# Altium_radio.net
KiCad netlist of a schematic drawn in Altium Designer
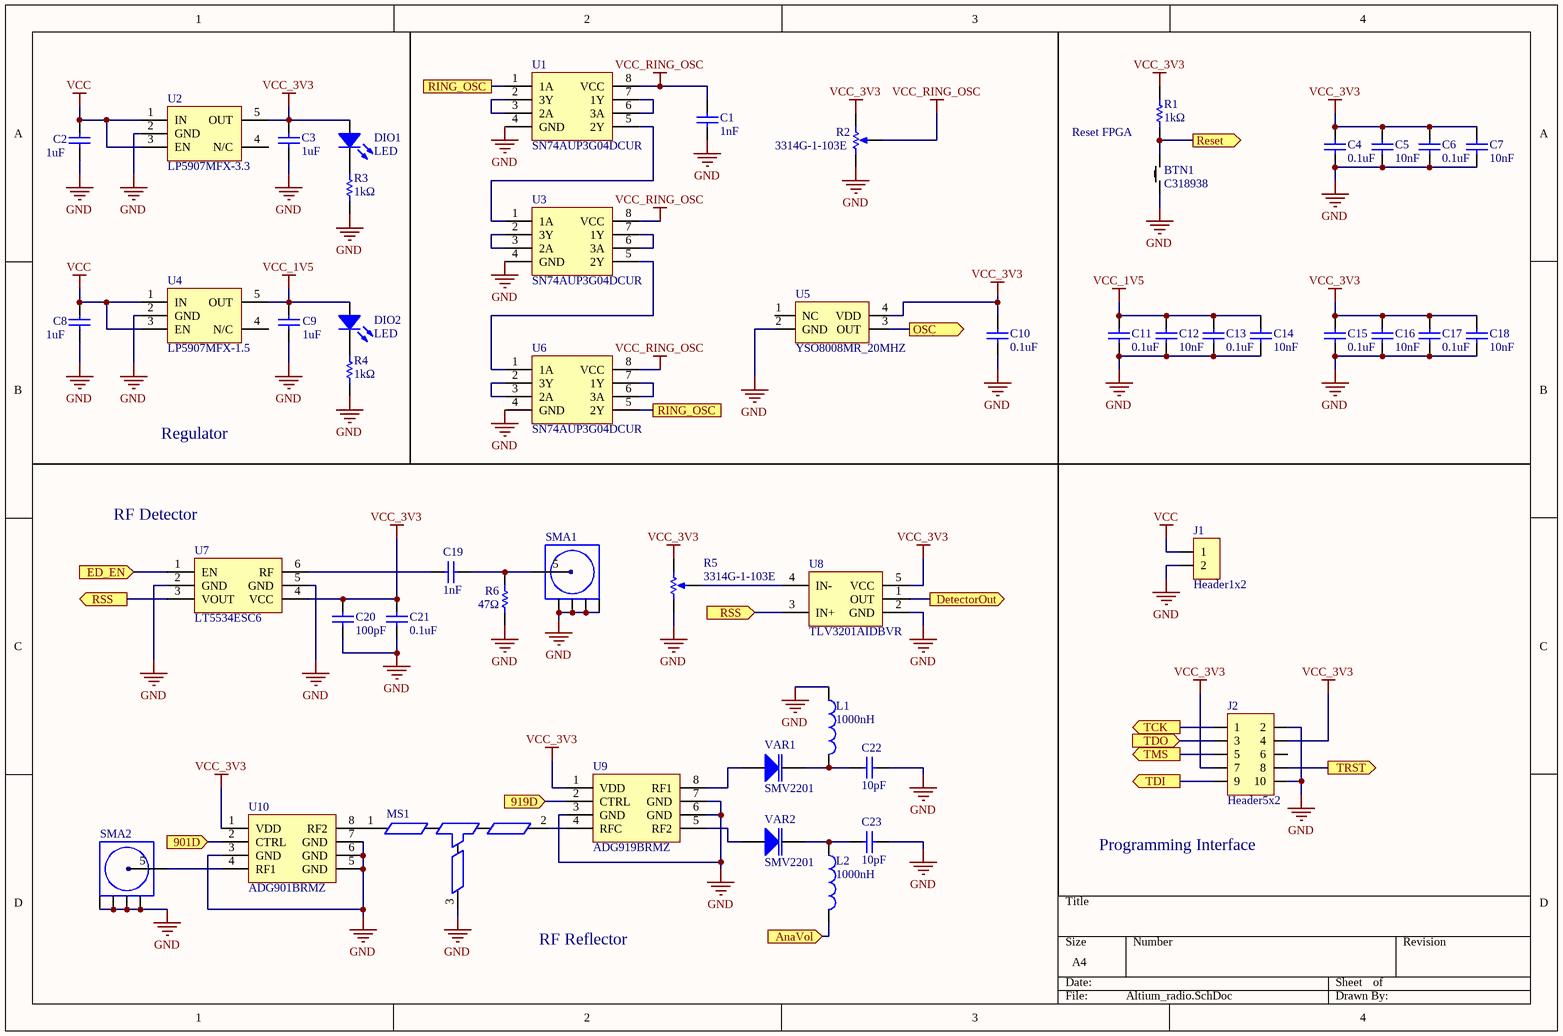
[diagram p0: Altium_radio.SchDoc]

(export (version "E")
  (design (tool "Eeschema 10.0.6"))
  (components
    (comp (ref "BTN1")
      (value "C318938")
      (footprint "C318938")
      (libsource (lib "backscatter") (part "C318938"))
    )
    (comp (ref "C1") (value "1nF") (footprint "C0603") (libsource (lib "backscatter") (part "Cap")))
    (comp (ref "C2") (value "1uF") (footprint "C0603") (libsource (lib "backscatter") (part "Cap")))
    (comp (ref "C3") (value "1uF") (footprint "C0603") (libsource (lib "backscatter") (part "Cap")))
    (comp (ref "C4") (value "0.1uF") (footprint "C0603") (libsource (lib "backscatter") (part "Cap")))
    (comp (ref "C5") (value "10nF") (footprint "C0603") (libsource (lib "backscatter") (part "Cap")))
    (comp (ref "C6") (value "0.1uF") (footprint "C0603") (libsource (lib "backscatter") (part "Cap")))
    (comp (ref "C7") (value "10nF") (footprint "C0603") (libsource (lib "backscatter") (part "Cap")))
    (comp (ref "C8") (value "1uF") (footprint "C0603") (libsource (lib "backscatter") (part "Cap")))
    (comp (ref "C9") (value "1uF") (footprint "C0603") (libsource (lib "backscatter") (part "Cap")))
    (comp (ref "C10") (value "0.1uF") (footprint "C0603") (libsource (lib "backscatter") (part "Cap")))
    (comp (ref "C11") (value "0.1uF") (footprint "C0603") (libsource (lib "backscatter") (part "Cap")))
    (comp (ref "C12") (value "10nF") (footprint "C0603") (libsource (lib "backscatter") (part "Cap")))
    (comp (ref "C13") (value "0.1uF") (footprint "C0603") (libsource (lib "backscatter") (part "Cap")))
    (comp (ref "C14") (value "10nF") (footprint "C0603") (libsource (lib "backscatter") (part "Cap")))
    (comp (ref "C15") (value "0.1uF") (footprint "C0603") (libsource (lib "backscatter") (part "Cap")))
    (comp (ref "C16") (value "10nF") (footprint "C0603") (libsource (lib "backscatter") (part "Cap")))
    (comp (ref "C17") (value "0.1uF") (footprint "C0603") (libsource (lib "backscatter") (part "Cap")))
    (comp (ref "C18") (value "10nF") (footprint "C0603") (libsource (lib "backscatter") (part "Cap")))
    (comp (ref "C19") (value "1nF") (footprint "C0603") (libsource (lib "backscatter") (part "Cap")))
    (comp (ref "C20") (value "100pF") (footprint "C0402") (libsource (lib "backscatter") (part "Cap")))
    (comp (ref "C21") (value "0.1uF") (footprint "C0603") (libsource (lib "backscatter") (part "Cap")))
    (comp (ref "C22") (value "10pF") (footprint "C0402") (libsource (lib "backscatter") (part "Cap")))
    (comp (ref "C23") (value "10pF") (footprint "C0402") (libsource (lib "backscatter") (part "Cap")))
    (comp (ref "DIO1") (value "LED") (footprint "LED0603") (libsource (lib "backscatter") (part "LED")))
    (comp (ref "DIO2") (value "LED") (footprint "LED0603") (libsource (lib "backscatter") (part "LED")))
    (comp (ref "J1")
      (value "Header1x2")
      (footprint "Header1x2")
      (libsource (lib "backscatter") (part "Header1x2"))
    )
    (comp (ref "J2")
      (value "Header5x2")
      (footprint "Header2x5")
      (libsource (lib "backscatter") (part "Header5x2"))
    )
    (comp (ref "L1") (value "1000nH") (footprint "L0805") (libsource (lib "backscatter") (part "Inductor")))
    (comp (ref "L2") (value "1000nH") (footprint "L0805") (libsource (lib "backscatter") (part "Inductor")))
    (comp (ref "MS1") (value "MSTEE") (footprint "MTEE_SMA") (libsource (lib "backscatter") (part "MSTEE")))
    (comp (ref "R1") (value "1kΩ") (footprint "R0603") (libsource (lib "backscatter") (part "Res")))
    (comp (ref "R2")
      (value "3314G-1-103E")
      (footprint "3314G-1-103E")
      (libsource (lib "backscatter") (part "3314G-1-103E"))
    )
    (comp (ref "R3") (value "1kΩ") (footprint "R0603") (libsource (lib "backscatter") (part "Res")))
    (comp (ref "R4") (value "1kΩ") (footprint "R0603") (libsource (lib "backscatter") (part "Res")))
    (comp (ref "R5")
      (value "3314G-1-103E")
      (footprint "3314G-1-103E")
      (libsource (lib "backscatter") (part "3314G-1-103E"))
    )
    (comp (ref "R6") (value "47Ω") (footprint "R0603") (libsource (lib "backscatter") (part "Res")))
    (comp (ref "SMA1") (value "SMA") (footprint "HJ-SMA305") (libsource (lib "") (part "SMA_1")))
    (comp (ref "SMA2") (value "SMA") (footprint "HJ-SMA305") (libsource (lib "backscatter") (part "SMA")))
    (comp (ref "U1")
      (value "SN74AUP3G04DCUR")
      (footprint "SN74AUP3G04DCUR")
      (libsource (lib "backscatter") (part "SN74AUP3G04DCUR"))
    )
    (comp (ref "U2")
      (value "LP5907MFX-3.3")
      (footprint "LP5907MFX-3.3")
      (libsource (lib "backscatter") (part "LP5907MFX-3.3"))
    )
    (comp (ref "U3")
      (value "SN74AUP3G04DCUR")
      (footprint "SN74AUP3G04DCUR")
      (libsource (lib "backscatter") (part "SN74AUP3G04DCUR"))
    )
    (comp (ref "U4")
      (value "LP5907MFX-1.5")
      (footprint "LP5907MFX-1.5")
      (libsource (lib "backscatter") (part "LP5907MFX-1.5"))
    )
    (comp (ref "U5")
      (value "YSO8008MR_20MHZ")
      (footprint "YSO8008MR_20MHz")
      (libsource (lib "backscatter") (part "YSO8008MR_20MHZ"))
    )
    (comp (ref "U6")
      (value "SN74AUP3G04DCUR")
      (footprint "SN74AUP3G04DCUR")
      (libsource (lib "backscatter") (part "SN74AUP3G04DCUR"))
    )
    (comp (ref "U7")
      (value "LT5534ESC6")
      (footprint "LT5534ESC6#TRPBF")
      (libsource (lib "backscatter") (part "LT5534ESC6"))
    )
    (comp (ref "U8")
      (value "TLV3201AIDBVR")
      (footprint "TLV3201AIDBVR")
      (libsource (lib "backscatter") (part "TLV3201AIDBVR"))
    )
    (comp (ref "U9")
      (value "ADG919BRMZ")
      (footprint "ADG919BRMZ")
      (libsource (lib "backscatter") (part "ADG919BRMZ"))
    )
    (comp (ref "U10")
      (value "ADG901BRMZ")
      (footprint "ADG901BRMZ-REEL7")
      (libsource (lib "backscatter") (part "ADG901BRMZ"))
    )
    (comp (ref "VAR1") (value "SMV2201") (footprint "D0402") (libsource (lib "backscatter") (part "VAR")))
    (comp (ref "VAR2") (value "SMV2201") (footprint "D0402") (libsource (lib "backscatter") (part "VAR")))
  )
  (nets
    (net (code "1") (name "/901D") (class "Default")
      (node (ref "U10") (pin "2") (pinfunction "CTRL_2") (pintype "passive"))
    )
    (net (code "2") (name "/919D") (class "Default")
      (node (ref "U9") (pin "2") (pinfunction "CTRL_2") (pintype "passive"))
    )
    (net (code "3") (name "/AnaVol") (class "Default")
      (node (ref "L2") (pin "2") (pinfunction "2_2") (pintype "passive"))
    )
    (net (code "4") (name "/DetectorOut") (class "Default")
      (node (ref "U8") (pin "1") (pinfunction "OUT_1") (pintype "passive"))
    )
    (net (code "5") (name "/ED_EN") (class "Default")
      (node (ref "U7") (pin "1") (pinfunction "EN_1") (pintype "passive"))
    )
    (net (code "6") (name "/OSC") (class "Default")
      (node (ref "U5") (pin "3") (pinfunction "OUT_3") (pintype "passive"))
    )
    (net (code "7") (name "/RING_OSC") (class "Default")
      (node (ref "U1") (pin "1") (pinfunction "1A_1") (pintype "passive"))
      (node (ref "U6") (pin "5") (pinfunction "2Y_5") (pintype "passive"))
    )
    (net (code "8") (name "/RSS") (class "Default")
      (node (ref "U7") (pin "3") (pinfunction "VOUT_3") (pintype "passive"))
      (node (ref "U8") (pin "3") (pinfunction "IN+_3") (pintype "passive"))
    )
    (net (code "9") (name "/Reset") (class "Default")
      (node (ref "BTN1") (pin "2") (pinfunction "2_2") (pintype "passive"))
      (node (ref "R1") (pin "1") (pinfunction "1_1") (pintype "passive"))
    )
    (net (code "10") (name "/TCK") (class "Default")
      (node (ref "J2") (pin "1") (pinfunction "1_1") (pintype "passive"))
    )
    (net (code "11") (name "/TDI") (class "Default")
      (node (ref "J2") (pin "9") (pinfunction "9_9") (pintype "passive"))
    )
    (net (code "12") (name "/TDO") (class "Default")
      (node (ref "J2") (pin "3") (pinfunction "3_3") (pintype "passive"))
    )
    (net (code "13") (name "/TMS") (class "Default")
      (node (ref "J2") (pin "5") (pinfunction "5_5") (pintype "passive"))
    )
    (net (code "14") (name "/TRST") (class "Default")
      (node (ref "J2") (pin "8") (pinfunction "8_8") (pintype "passive"))
    )
    (net (code "15") (name "GND") (class "Default")
      (node (ref "BTN1") (pin "1") (pinfunction "1_1") (pintype "passive"))
      (node (ref "C1") (pin "1") (pinfunction "1_1") (pintype "passive"))
      (node (ref "C10") (pin "2") (pinfunction "2_2") (pintype "passive"))
      (node (ref "C11") (pin "2") (pinfunction "2_2") (pintype "passive"))
      (node (ref "C12") (pin "2") (pinfunction "2_2") (pintype "passive"))
      (node (ref "C13") (pin "2") (pinfunction "2_2") (pintype "passive"))
      (node (ref "C14") (pin "2") (pinfunction "2_2") (pintype "passive"))
      (node (ref "C15") (pin "2") (pinfunction "2_2") (pintype "passive"))
      (node (ref "C16") (pin "2") (pinfunction "2_2") (pintype "passive"))
      (node (ref "C17") (pin "2") (pinfunction "2_2") (pintype "passive"))
      (node (ref "C18") (pin "2") (pinfunction "2_2") (pintype "passive"))
      (node (ref "C2") (pin "1") (pinfunction "1_1") (pintype "passive"))
      (node (ref "C20") (pin "1") (pinfunction "1_1") (pintype "passive"))
      (node (ref "C21") (pin "1") (pinfunction "1_1") (pintype "passive"))
      (node (ref "C22") (pin "2") (pinfunction "2_2") (pintype "passive"))
      (node (ref "C23") (pin "2") (pinfunction "2_2") (pintype "passive"))
      (node (ref "C3") (pin "1") (pinfunction "1_1") (pintype "passive"))
      (node (ref "C4") (pin "2") (pinfunction "2_2") (pintype "passive"))
      (node (ref "C5") (pin "2") (pinfunction "2_2") (pintype "passive"))
      (node (ref "C6") (pin "2") (pinfunction "2_2") (pintype "passive"))
      (node (ref "C7") (pin "2") (pinfunction "2_2") (pintype "passive"))
      (node (ref "C8") (pin "1") (pinfunction "1_1") (pintype "passive"))
      (node (ref "C9") (pin "1") (pinfunction "1_1") (pintype "passive"))
      (node (ref "J1") (pin "2") (pinfunction "2_2") (pintype "passive"))
      (node (ref "J2") (pin "10") (pinfunction "10_10") (pintype "passive"))
      (node (ref "J2") (pin "2") (pinfunction "2_2") (pintype "passive"))
      (node (ref "L1") (pin "1") (pinfunction "1_1") (pintype "passive"))
      (node (ref "MS1") (pin "3") (pinfunction "3_3") (pintype "passive"))
      (node (ref "R2") (pin "3") (pinfunction "CW_3") (pintype "passive"))
      (node (ref "R3") (pin "1") (pinfunction "1_1") (pintype "passive"))
      (node (ref "R4") (pin "1") (pinfunction "1_1") (pintype "passive"))
      (node (ref "R5") (pin "3") (pinfunction "CW_3") (pintype "passive"))
      (node (ref "R6") (pin "1") (pinfunction "1_1") (pintype "passive"))
      (node (ref "SMA1") (pin "1") (pinfunction "GND_1") (pintype "power_in"))
      (node (ref "SMA1") (pin "2") (pinfunction "GND_2") (pintype "power_in"))
      (node (ref "SMA1") (pin "3") (pinfunction "GND_3") (pintype "power_in"))
      (node (ref "SMA1") (pin "4") (pinfunction "GND_4") (pintype "power_in"))
      (node (ref "SMA2") (pin "1") (pinfunction "GND_1") (pintype "power_in"))
      (node (ref "SMA2") (pin "2") (pinfunction "GND_2") (pintype "power_in"))
      (node (ref "SMA2") (pin "3") (pinfunction "GND_3") (pintype "power_in"))
      (node (ref "SMA2") (pin "4") (pinfunction "GND_4") (pintype "power_in"))
      (node (ref "U1") (pin "4") (pinfunction "GND_4") (pintype "power_in"))
      (node (ref "U10") (pin "3") (pinfunction "GND_3") (pintype "power_in"))
      (node (ref "U10") (pin "5") (pinfunction "GND_5") (pintype "power_in"))
      (node (ref "U10") (pin "6") (pinfunction "GND_6") (pintype "power_in"))
      (node (ref "U10") (pin "7") (pinfunction "GND_7") (pintype "power_in"))
      (node (ref "U2") (pin "2") (pinfunction "GND_2") (pintype "power_in"))
      (node (ref "U3") (pin "4") (pinfunction "GND_4") (pintype "power_in"))
      (node (ref "U4") (pin "2") (pinfunction "GND_2") (pintype "power_in"))
      (node (ref "U5") (pin "2") (pinfunction "GND_2") (pintype "passive"))
      (node (ref "U6") (pin "4") (pinfunction "GND_4") (pintype "power_in"))
      (node (ref "U7") (pin "2") (pinfunction "GND_2") (pintype "power_in"))
      (node (ref "U7") (pin "5") (pinfunction "GND_5") (pintype "power_in"))
      (node (ref "U8") (pin "2") (pinfunction "GND_2") (pintype "power_in"))
      (node (ref "U9") (pin "3") (pinfunction "GND_3") (pintype "power_in"))
      (node (ref "U9") (pin "6") (pinfunction "GND_6") (pintype "power_in"))
      (node (ref "U9") (pin "7") (pinfunction "GND_7") (pintype "power_in"))
    )
    (net (code "16") (name "Net-(DIO1-*-Pad2)") (class "Default")
      (node (ref "DIO1") (pin "2") (pinfunction "*_2") (pintype "passive"))
      (node (ref "R3") (pin "2") (pinfunction "2_2") (pintype "passive"))
    )
    (net (code "17") (name "Net-(DIO2-*-Pad2)") (class "Default")
      (node (ref "DIO2") (pin "2") (pinfunction "*_2") (pintype "passive"))
      (node (ref "R4") (pin "2") (pinfunction "2_2") (pintype "passive"))
    )
    (net (code "18") (name "Net-(R5-WIPER)") (class "Default")
      (node (ref "R5") (pin "2") (pinfunction "WIPER_2") (pintype "passive"))
      (node (ref "U8") (pin "4") (pinfunction "IN-_4") (pintype "passive"))
    )
    (net (code "19") (name "Net-(SMA1-SMA_CON)") (class "Default")
      (node (ref "C19") (pin "2") (pinfunction "2_2") (pintype "passive"))
      (node (ref "R6") (pin "2") (pinfunction "2_2") (pintype "passive"))
      (node (ref "SMA1") (pin "5") (pinfunction "SMA_CON_5") (pintype "passive"))
    )
    (net (code "20") (name "Net-(SMA2-SMA_CON)") (class "Default")
      (node (ref "SMA2") (pin "5") (pinfunction "SMA_CON_5") (pintype "passive"))
      (node (ref "U10") (pin "4") (pinfunction "RF1_4") (pintype "passive"))
    )
    (net (code "21") (name "Net-(U1-1Y)") (class "Default")
      (node (ref "U1") (pin "6") (pinfunction "3A_6") (pintype "passive"))
      (node (ref "U1") (pin "7") (pinfunction "1Y_7") (pintype "passive"))
    )
    (net (code "22") (name "Net-(U1-2A)") (class "Default")
      (node (ref "U1") (pin "2") (pinfunction "3Y_2") (pintype "passive"))
      (node (ref "U1") (pin "3") (pinfunction "2A_3") (pintype "passive"))
    )
    (net (code "23") (name "Net-(U1-2Y)") (class "Default")
      (node (ref "U1") (pin "5") (pinfunction "2Y_5") (pintype "passive"))
      (node (ref "U3") (pin "1") (pinfunction "1A_1") (pintype "passive"))
    )
    (net (code "24") (name "Net-(U3-1Y)") (class "Default")
      (node (ref "U3") (pin "6") (pinfunction "3A_6") (pintype "passive"))
      (node (ref "U3") (pin "7") (pinfunction "1Y_7") (pintype "passive"))
    )
    (net (code "25") (name "Net-(U3-2A)") (class "Default")
      (node (ref "U3") (pin "2") (pinfunction "3Y_2") (pintype "passive"))
      (node (ref "U3") (pin "3") (pinfunction "2A_3") (pintype "passive"))
    )
    (net (code "26") (name "Net-(U3-2Y)") (class "Default")
      (node (ref "U3") (pin "5") (pinfunction "2Y_5") (pintype "passive"))
      (node (ref "U6") (pin "1") (pinfunction "1A_1") (pintype "passive"))
    )
    (net (code "27") (name "Net-(U6-1Y)") (class "Default")
      (node (ref "U6") (pin "6") (pinfunction "3A_6") (pintype "passive"))
      (node (ref "U6") (pin "7") (pinfunction "1Y_7") (pintype "passive"))
    )
    (net (code "28") (name "Net-(U6-2A)") (class "Default")
      (node (ref "U6") (pin "2") (pinfunction "3Y_2") (pintype "passive"))
      (node (ref "U6") (pin "3") (pinfunction "2A_3") (pintype "passive"))
    )
    (net (code "29") (name "Net-(U7-RF)") (class "Default")
      (node (ref "C19") (pin "1") (pinfunction "1_1") (pintype "passive"))
      (node (ref "U7") (pin "6") (pinfunction "RF_6") (pintype "passive"))
    )
    (net (code "30") (name "Net-(U9-RF1)") (class "Default")
      (node (ref "U9") (pin "8") (pinfunction "RF1_8") (pintype "passive"))
      (node (ref "VAR1") (pin "2") (pinfunction "A_2") (pintype "passive"))
    )
    (net (code "31") (name "Net-(U9-RF2)") (class "Default")
      (node (ref "U9") (pin "5") (pinfunction "RF2_5") (pintype "passive"))
      (node (ref "VAR2") (pin "2") (pinfunction "A_2") (pintype "passive"))
    )
    (net (code "32") (name "Net-(U9-RFC)") (class "Default")
      (node (ref "MS1") (pin "2") (pinfunction "2_2") (pintype "passive"))
      (node (ref "U9") (pin "4") (pinfunction "RFC_4") (pintype "passive"))
    )
    (net (code "33") (name "Net-(U10-RF2)") (class "Default")
      (node (ref "MS1") (pin "1") (pinfunction "1_1") (pintype "passive"))
      (node (ref "U10") (pin "8") (pinfunction "RF2_8") (pintype "passive"))
    )
    (net (code "34") (name "Net-(VAR1-K)") (class "Default")
      (node (ref "C22") (pin "1") (pinfunction "1_1") (pintype "passive"))
      (node (ref "L1") (pin "2") (pinfunction "2_2") (pintype "passive"))
      (node (ref "VAR1") (pin "1") (pinfunction "K_1") (pintype "passive"))
    )
    (net (code "35") (name "Net-(VAR2-K)") (class "Default")
      (node (ref "C23") (pin "1") (pinfunction "1_1") (pintype "passive"))
      (node (ref "L2") (pin "1") (pinfunction "1_1") (pintype "passive"))
      (node (ref "VAR2") (pin "1") (pinfunction "K_1") (pintype "passive"))
    )
    (net (code "36") (name "VCC") (class "Default")
      (node (ref "C2") (pin "2") (pinfunction "2_2") (pintype "passive"))
      (node (ref "C8") (pin "2") (pinfunction "2_2") (pintype "passive"))
      (node (ref "J1") (pin "1") (pinfunction "1_1") (pintype "passive"))
      (node (ref "U2") (pin "1") (pinfunction "IN_1") (pintype "passive"))
      (node (ref "U2") (pin "3") (pinfunction "EN_3") (pintype "passive"))
      (node (ref "U4") (pin "1") (pinfunction "IN_1") (pintype "passive"))
      (node (ref "U4") (pin "3") (pinfunction "EN_3") (pintype "passive"))
    )
    (net (code "37") (name "VCC_1V5") (class "Default")
      (node (ref "C11") (pin "1") (pinfunction "1_1") (pintype "passive"))
      (node (ref "C12") (pin "1") (pinfunction "1_1") (pintype "passive"))
      (node (ref "C13") (pin "1") (pinfunction "1_1") (pintype "passive"))
      (node (ref "C14") (pin "1") (pinfunction "1_1") (pintype "passive"))
      (node (ref "C9") (pin "2") (pinfunction "2_2") (pintype "passive"))
      (node (ref "DIO2") (pin "1") (pinfunction "*_1") (pintype "passive"))
      (node (ref "U4") (pin "5") (pinfunction "OUT_5") (pintype "passive"))
    )
    (net (code "38") (name "VCC_3V3") (class "Default")
      (node (ref "C10") (pin "1") (pinfunction "1_1") (pintype "passive"))
      (node (ref "C15") (pin "1") (pinfunction "1_1") (pintype "passive"))
      (node (ref "C16") (pin "1") (pinfunction "1_1") (pintype "passive"))
      (node (ref "C17") (pin "1") (pinfunction "1_1") (pintype "passive"))
      (node (ref "C18") (pin "1") (pinfunction "1_1") (pintype "passive"))
      (node (ref "C20") (pin "2") (pinfunction "2_2") (pintype "passive"))
      (node (ref "C21") (pin "2") (pinfunction "2_2") (pintype "passive"))
      (node (ref "C3") (pin "2") (pinfunction "2_2") (pintype "passive"))
      (node (ref "C4") (pin "1") (pinfunction "1_1") (pintype "passive"))
      (node (ref "C5") (pin "1") (pinfunction "1_1") (pintype "passive"))
      (node (ref "C6") (pin "1") (pinfunction "1_1") (pintype "passive"))
      (node (ref "C7") (pin "1") (pinfunction "1_1") (pintype "passive"))
      (node (ref "DIO1") (pin "1") (pinfunction "*_1") (pintype "passive"))
      (node (ref "J2") (pin "4") (pinfunction "4_4") (pintype "passive"))
      (node (ref "J2") (pin "7") (pinfunction "7_7") (pintype "passive"))
      (node (ref "R1") (pin "2") (pinfunction "2_2") (pintype "passive"))
      (node (ref "R2") (pin "1") (pinfunction "CCW_1") (pintype "passive"))
      (node (ref "R5") (pin "1") (pinfunction "CCW_1") (pintype "passive"))
      (node (ref "U10") (pin "1") (pinfunction "VDD_1") (pintype "power_in"))
      (node (ref "U2") (pin "5") (pinfunction "OUT_5") (pintype "passive"))
      (node (ref "U5") (pin "4") (pinfunction "VDD_4") (pintype "passive"))
      (node (ref "U7") (pin "4") (pinfunction "VCC_4") (pintype "power_in"))
      (node (ref "U8") (pin "5") (pinfunction "VCC_5") (pintype "power_in"))
      (node (ref "U9") (pin "1") (pinfunction "VDD_1") (pintype "power_in"))
    )
    (net (code "39") (name "VCC_RING_OSC") (class "Default")
      (node (ref "C1") (pin "2") (pinfunction "2_2") (pintype "passive"))
      (node (ref "R2") (pin "2") (pinfunction "WIPER_2") (pintype "passive"))
      (node (ref "U1") (pin "8") (pinfunction "VCC_8") (pintype "power_in"))
      (node (ref "U3") (pin "8") (pinfunction "VCC_8") (pintype "power_in"))
      (node (ref "U6") (pin "8") (pinfunction "VCC_8") (pintype "power_in"))
    )
    (net (code "40") (name "unconnected-(J2-Pad6)") (class "Default")
      (node (ref "J2") (pin "6") (pinfunction "6_6") (pintype "passive"))
    )
    (net (code "41") (name "unconnected-(U2-N{slash}C-Pad4)") (class "Default")
      (node (ref "U2") (pin "4") (pinfunction "N/C_4") (pintype "passive"))
    )
    (net (code "42") (name "unconnected-(U4-N{slash}C-Pad4)") (class "Default")
      (node (ref "U4") (pin "4") (pinfunction "N/C_4") (pintype "passive"))
    )
    (net (code "43") (name "unconnected-(U5-NC-Pad1)") (class "Default")
      (node (ref "U5") (pin "1") (pinfunction "NC_1") (pintype "passive"))
    )
  )
)
